# ExternalMotorControllerRev2.net
KiCad netlist of a schematic drawn in EAGLE
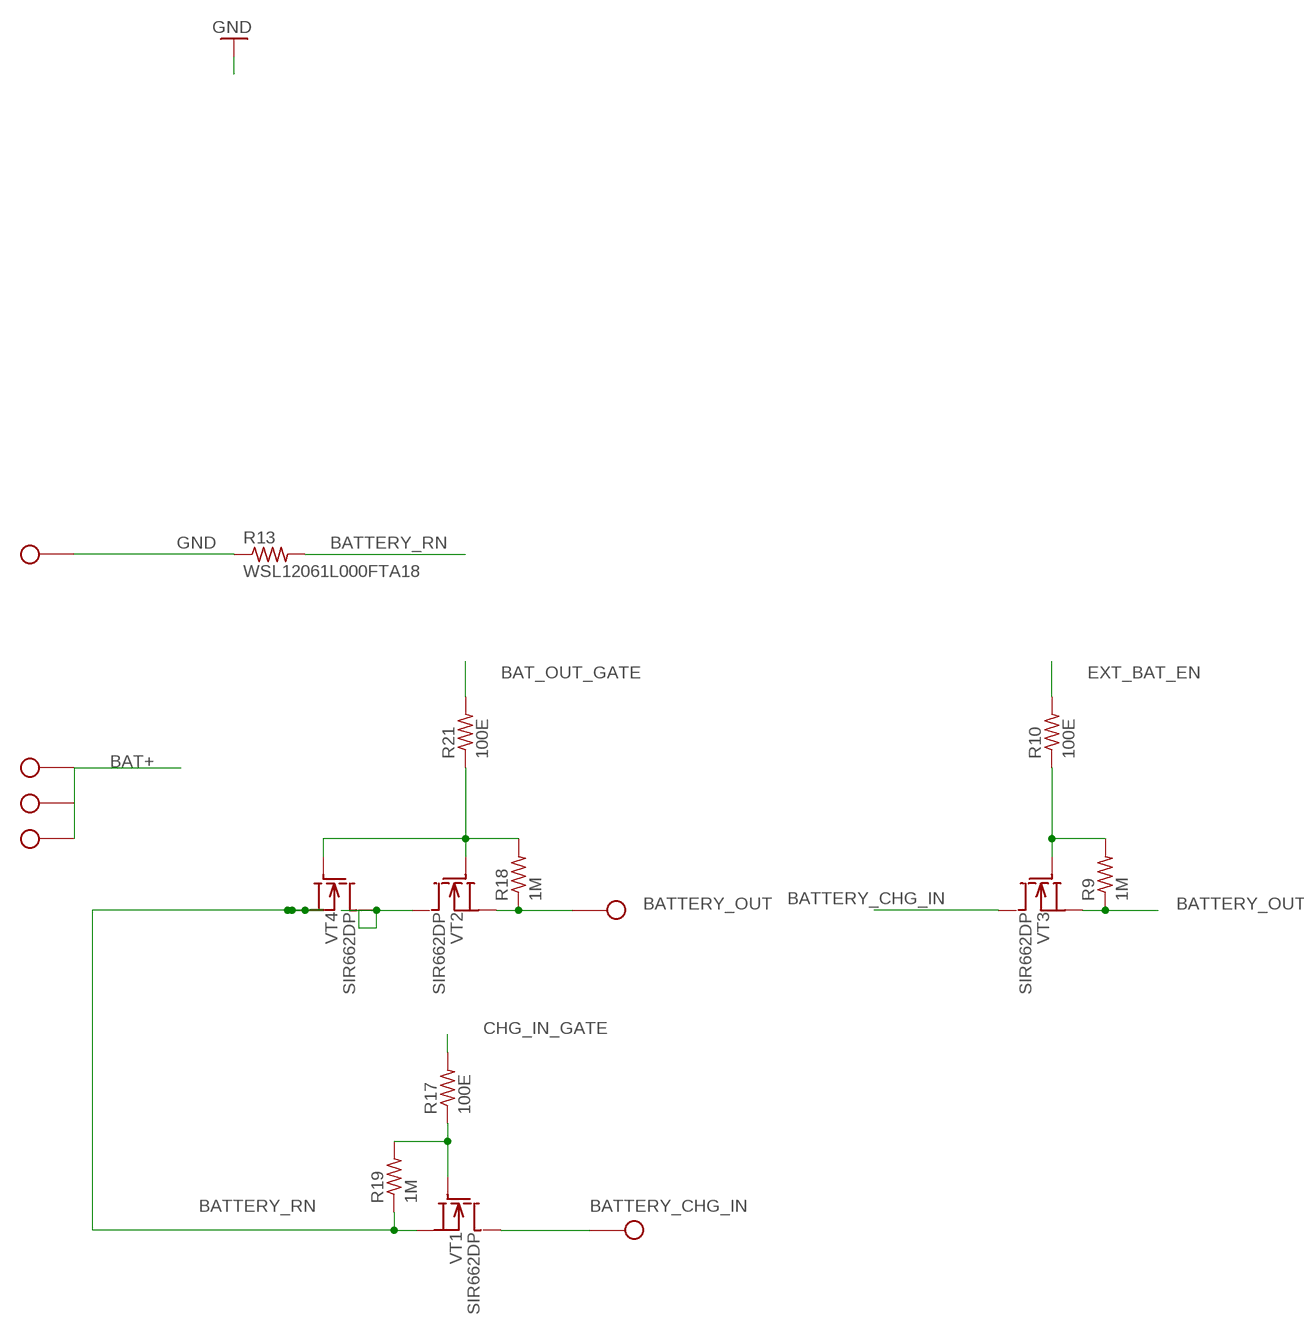
[diagram p0: schematic, sheet 1]
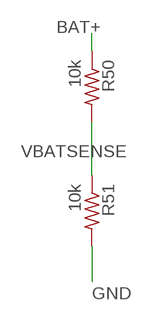
[diagram p1: schematic, sheet 3]
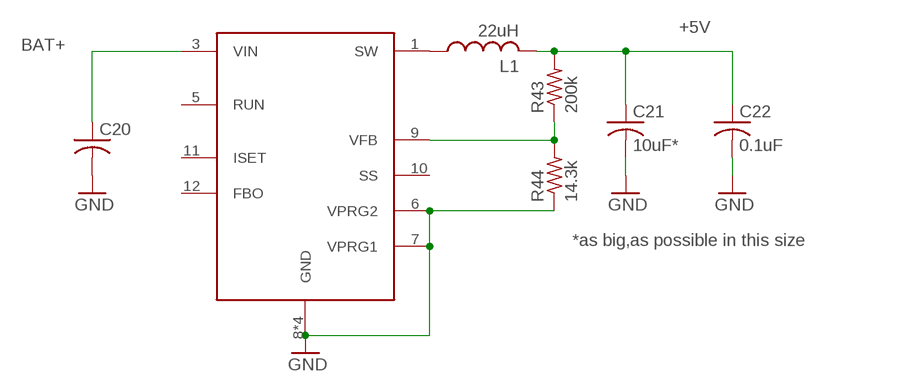
[diagram p2: schematic, sheet 4]
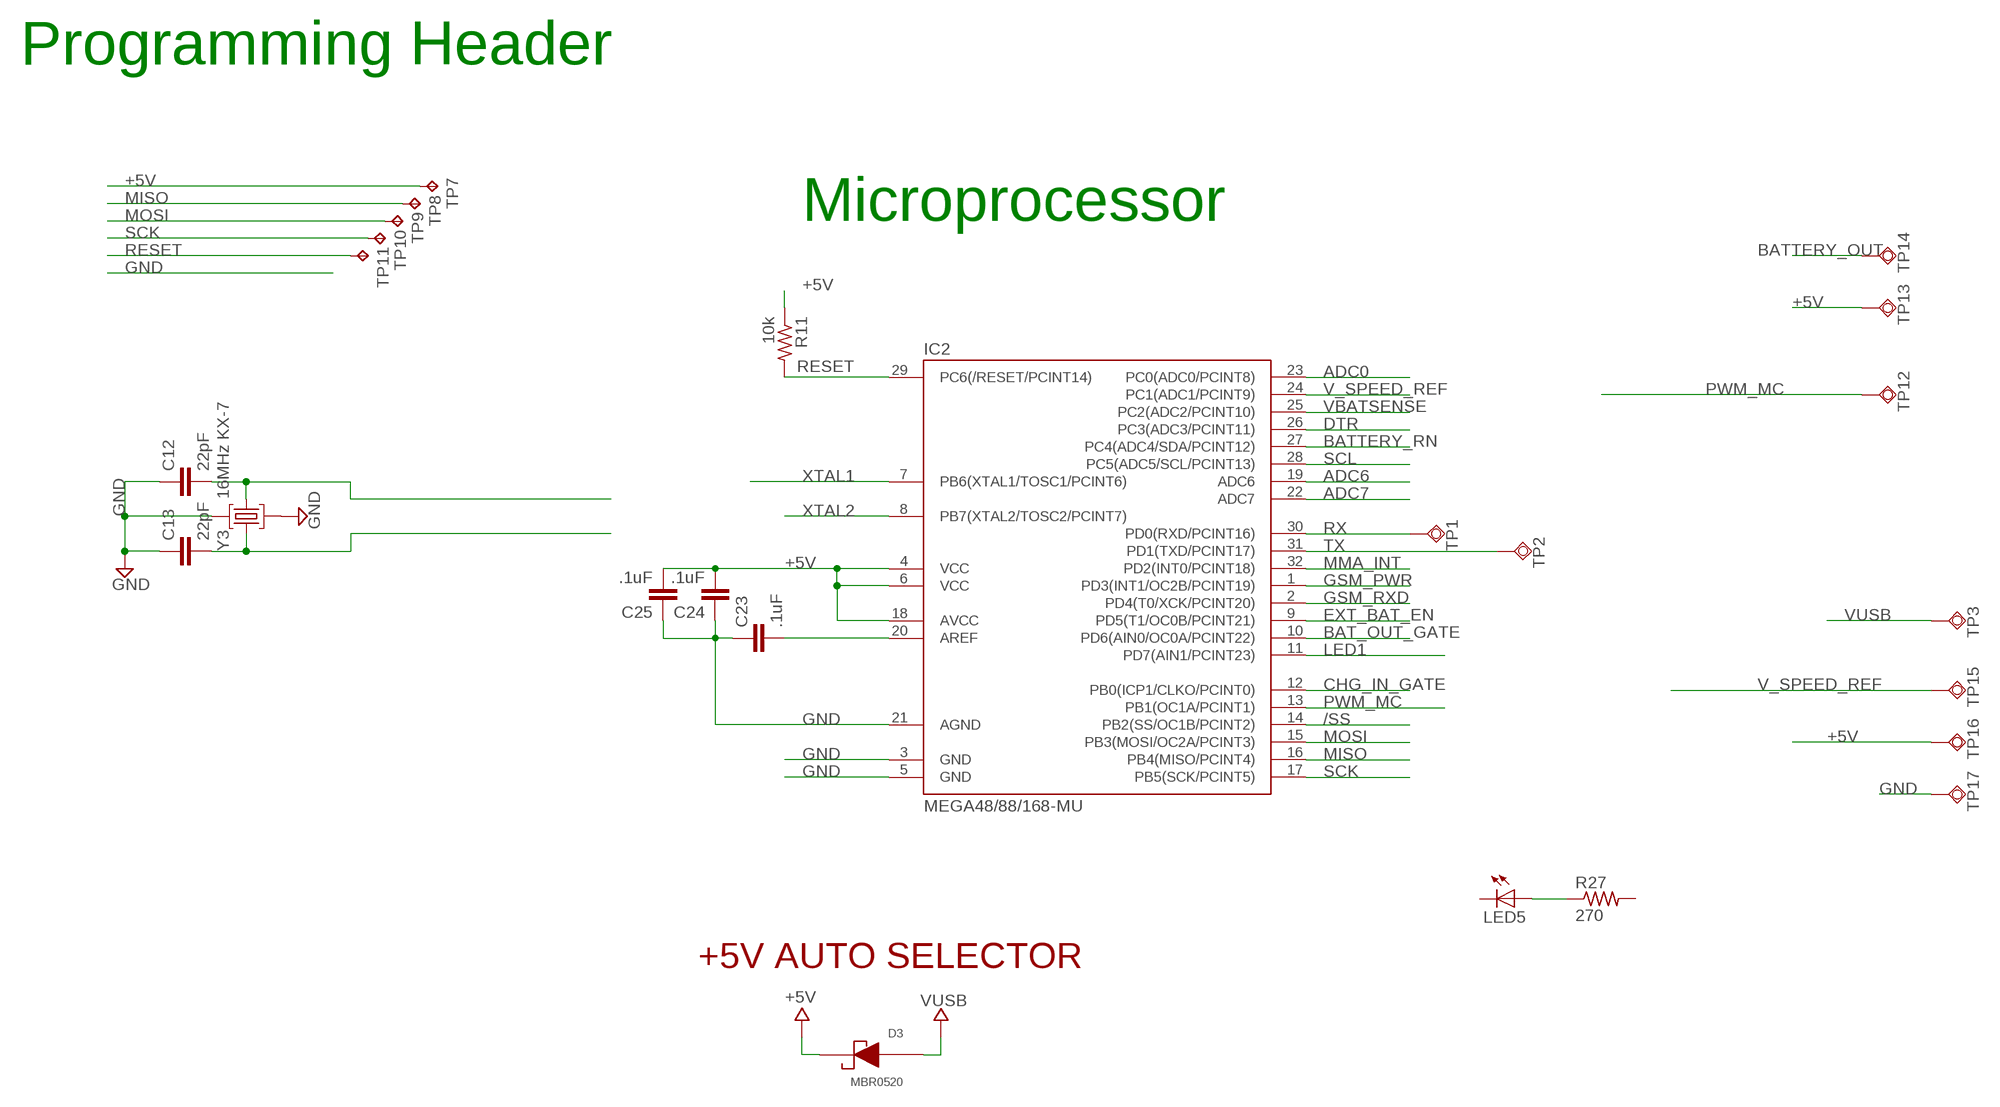
[diagram p3: schematic, sheet 7]

(export (version "E")
  (design (tool "Eeschema 10.0.6"))
  (components
    (comp (ref "R9")
      (value "1M")
      (footprint "eagle-import:R0402")
      (libsource (lib "eagle-import") (part "R-US_R0402"))
    )
    (comp (ref "R10")
      (value "100E")
      (footprint "eagle-import:R0402")
      (libsource (lib "eagle-import") (part "R-US_R0402"))
    )
    (comp (ref "R13")
      (value "WSL12061L000FTA18")
      (footprint "eagle-import:R2512")
      (libsource (lib "eagle-import") (part "R-US_R2512"))
    )
    (comp (ref "R17")
      (value "100E")
      (footprint "eagle-import:R0402")
      (libsource (lib "eagle-import") (part "R-US_R0402"))
    )
    (comp (ref "R18")
      (value "1M")
      (footprint "eagle-import:R0402")
      (libsource (lib "eagle-import") (part "R-US_R0402"))
    )
    (comp (ref "R19")
      (value "1M")
      (footprint "eagle-import:R0402")
      (libsource (lib "eagle-import") (part "R-US_R0402"))
    )
    (comp (ref "R21")
      (value "100E")
      (footprint "eagle-import:R0402")
      (libsource (lib "eagle-import") (part "R-US_R0402"))
    )
    (comp (ref "VT1")
      (value "SIR662DP")
      (footprint "eagle-import:POWERPAK_SO8")
      (libsource (lib "eagle-import") (part "SIR662DP"))
    )
    (comp (ref "VT2")
      (value "SIR662DP")
      (footprint "eagle-import:POWERPAK_SO8")
      (libsource (lib "eagle-import") (part "SIR662DP"))
    )
    (comp (ref "VT3")
      (value "SIR662DP")
      (footprint "eagle-import:POWERPAK_SO8")
      (libsource (lib "eagle-import") (part "SIR662DP"))
    )
    (comp (ref "VT4")
      (value "SIR662DP")
      (footprint "eagle-import:POWERPAK_SO8")
      (libsource (lib "eagle-import") (part "SIR662DP"))
    )
    (comp (ref "X1")
      (value "SOLDER_HOLE18AWG")
      (footprint "eagle-import:SOLDER_HOLE_18")
      (libsource (lib "eagle-import") (part "SOLDER_HOLE18AWG"))
    )
    (comp (ref "X2")
      (value "SOLDER_HOLE18AWG")
      (footprint "eagle-import:SOLDER_HOLE_18")
      (libsource (lib "eagle-import") (part "SOLDER_HOLE18AWG"))
    )
    (comp (ref "X3")
      (value "SOLDER_HOLE18AWG")
      (footprint "eagle-import:SOLDER_HOLE_18")
      (libsource (lib "eagle-import") (part "SOLDER_HOLE18AWG"))
    )
    (comp (ref "X4")
      (value "SOLDER_HOLE18AWG")
      (footprint "eagle-import:SOLDER_HOLE_18")
      (libsource (lib "eagle-import") (part "SOLDER_HOLE18AWG"))
    )
    (comp (ref "X5")
      (value "SOLDER_HOLE18AWG")
      (footprint "eagle-import:SOLDER_HOLE_18")
      (libsource (lib "eagle-import") (part "SOLDER_HOLE18AWG"))
    )
    (comp (ref "X13")
      (value "SOLDER_HOLE18AWG")
      (footprint "eagle-import:SOLDER_HOLE_18")
      (libsource (lib "eagle-import") (part "SOLDER_HOLE18AWG"))
    )
    (comp (ref "R50")
      (value "10k")
      (footprint "eagle-import:R0402")
      (libsource (lib "eagle-import") (part "rcl_R-US_R0402"))
    )
    (comp (ref "R51")
      (value "10k")
      (footprint "eagle-import:R0402")
      (libsource (lib "eagle-import") (part "rcl_R-US_R0402"))
    )
    (comp (ref "C12")
      (value "22pF")
      (footprint "eagle-import:C0402")
      (libsource (lib "eagle-import") (part "C-EUC0402"))
    )
    (comp (ref "C13")
      (value "22pF")
      (footprint "eagle-import:C0402")
      (libsource (lib "eagle-import") (part "C-EUC0402"))
    )
    (comp (ref "C23")
      (value ".1uF")
      (footprint "eagle-import:C0402")
      (libsource (lib "eagle-import") (part "rcl_C-EUC0402"))
    )
    (comp (ref "C24")
      (value ".1uF")
      (footprint "eagle-import:C0402")
      (libsource (lib "eagle-import") (part "rcl_C-EUC0402"))
    )
    (comp (ref "C25")
      (value ".1uF")
      (footprint "eagle-import:C0402")
      (libsource (lib "eagle-import") (part "rcl_C-EUC0402"))
    )
    (comp (ref "D3")
      (value "MBR0520")
      (footprint "eagle-import:SOD-123")
      (libsource (lib "eagle-import") (part "MBR0520"))
    )
    (comp (ref "IC2")
      (value "MEGA48/88/168-MU")
      (footprint "eagle-import:MLF32")
      (libsource (lib "eagle-import") (part "MEGA48/88/168-MU"))
    )
    (comp (ref "LED5")
      (value "LEDCHIP-LED0603")
      (footprint "eagle-import:CHIP-LED0603")
      (libsource (lib "eagle-import") (part "LEDCHIP-LED0603"))
    )
    (comp (ref "R11")
      (value "10k")
      (footprint "eagle-import:R0402")
      (libsource (lib "eagle-import") (part "rcl_R-US_R0402"))
    )
    (comp (ref "R27")
      (value "270")
      (footprint "eagle-import:R0402")
      (libsource (lib "eagle-import") (part "rcl_R-US_R0402"))
    )
    (comp (ref "TP1")
      (value "TPSQTP15R")
      (footprint "eagle-import:TP15R")
      (libsource (lib "eagle-import") (part "TPSQTP15R"))
    )
    (comp (ref "TP2")
      (value "TPSQTP15R")
      (footprint "eagle-import:TP15R")
      (libsource (lib "eagle-import") (part "TPSQTP15R"))
    )
    (comp (ref "TP3")
      (value "TPSQTP15R")
      (footprint "eagle-import:TP15R")
      (libsource (lib "eagle-import") (part "TPSQTP15R"))
    )
    (comp (ref "TP7")
      (value "TPTP08R")
      (footprint "eagle-import:TP08R")
      (libsource (lib "eagle-import") (part "TPTP08R"))
    )
    (comp (ref "TP8")
      (value "TPTP08R")
      (footprint "eagle-import:TP08R")
      (libsource (lib "eagle-import") (part "TPTP08R"))
    )
    (comp (ref "TP9")
      (value "TPTP08R")
      (footprint "eagle-import:TP08R")
      (libsource (lib "eagle-import") (part "TPTP08R"))
    )
    (comp (ref "TP10")
      (value "TPTP08R")
      (footprint "eagle-import:TP08R")
      (libsource (lib "eagle-import") (part "TPTP08R"))
    )
    (comp (ref "TP11")
      (value "TPTP10R")
      (footprint "eagle-import:TP10R")
      (libsource (lib "eagle-import") (part "TPTP10R"))
    )
    (comp (ref "TP12")
      (value "TPSQTP15SQ")
      (footprint "eagle-import:TP15SQ")
      (libsource (lib "eagle-import") (part "TPSQTP15SQ"))
    )
    (comp (ref "TP13")
      (value "TPSQTP15SQ")
      (footprint "eagle-import:TP15SQ")
      (libsource (lib "eagle-import") (part "TPSQTP15SQ"))
    )
    (comp (ref "TP14")
      (value "TPSQTP15SQ")
      (footprint "eagle-import:TP15SQ")
      (libsource (lib "eagle-import") (part "TPSQTP15SQ"))
    )
    (comp (ref "TP15")
      (value "TPSQTP15R")
      (footprint "eagle-import:TP15R")
      (libsource (lib "eagle-import") (part "TPSQTP15R"))
    )
    (comp (ref "TP16")
      (value "TPSQTP15SQ")
      (footprint "eagle-import:TP15SQ")
      (libsource (lib "eagle-import") (part "TPSQTP15SQ"))
    )
    (comp (ref "TP17")
      (value "TPSQTP15SQ")
      (footprint "eagle-import:TP15SQ")
      (libsource (lib "eagle-import") (part "TPSQTP15SQ"))
    )
    (comp (ref "Y3")
      (value "16MHz KX-7")
      (footprint "eagle-import:CRYSTAL-3.2-2.5")
      (libsource (lib "eagle-import") (part "CRYSTAL-3.2-2.5"))
    )
    (comp (ref "C20")
      (value "RCL_C-USC0805")
      (footprint "eagle-import:RCL_C0805$1")
      (libsource (lib "eagle-import") (part "RCL_C-USC0805"))
    )
    (comp (ref "C21")
      (value "10uF*")
      (footprint "eagle-import:RCL_C4532$1")
      (libsource (lib "eagle-import") (part "RCL_C-USC4532"))
    )
    (comp (ref "C22")
      (value "0.1uF")
      (footprint "eagle-import:C0402")
      (libsource (lib "eagle-import") (part "C-USC0402"))
    )
    (comp (ref "DA2")
      (value "LTC3630")
      (footprint "eagle-import:MSE16(12)")
      (libsource (lib "eagle-import") (part "LTC3630"))
    )
    (comp (ref "L1")
      (value "22uH")
      (footprint "eagle-import:M-PAD-2.1_1210")
      (libsource (lib "eagle-import") (part "M-PAD-2.1_L_USD"))
    )
    (comp (ref "R43")
      (value "200k")
      (footprint "eagle-import:RCL_R0402")
      (libsource (lib "eagle-import") (part "RCL_R-US_R0402"))
    )
    (comp (ref "R44")
      (value "14.3k")
      (footprint "eagle-import:RCL_R0402")
      (libsource (lib "eagle-import") (part "RCL_R-US_R0402"))
    )
  )
  (nets
    (net (code "1") (name "+5V") (class "Default")
      (node (ref "C21") (pin "1") (pinfunction "1_1") (pintype "passive"))
      (node (ref "C22") (pin "1") (pinfunction "1_1") (pintype "passive"))
      (node (ref "C24") (pin "2") (pinfunction "2_2") (pintype "passive"))
      (node (ref "C25") (pin "2") (pinfunction "2_2") (pintype "passive"))
      (node (ref "D3") (pin "1") (pinfunction "CA_1") (pintype "passive"))
      (node (ref "IC2") (pin "18") (pinfunction "AVCC_18") (pintype "passive"))
      (node (ref "IC2") (pin "4") (pinfunction "VCC_4") (pintype "power_in"))
      (node (ref "IC2") (pin "6") (pinfunction "VCC_6") (pintype "power_in"))
      (node (ref "L1") (pin "2") (pinfunction "2_2") (pintype "passive"))
      (node (ref "R11") (pin "1") (pinfunction "1_1") (pintype "passive"))
      (node (ref "R43") (pin "2") (pinfunction "2_2") (pintype "passive"))
      (node (ref "TP13") (pin "TP") (pinfunction "TP_TP") (pintype "input"))
      (node (ref "TP16") (pin "TP") (pinfunction "TP_TP") (pintype "input"))
      (node (ref "TP7") (pin "TP") (pinfunction "TP_TP") (pintype "input"))
    )
    (net (code "2") (name "ADC0") (class "Default")
      (node (ref "IC2") (pin "23") (pinfunction "PC0(ADC0/PCINT8)_23") (pintype "bidirectional"))
    )
    (net (code "3") (name "ADC6") (class "Default")
      (node (ref "IC2") (pin "19") (pinfunction "ADC6_19") (pintype "passive"))
    )
    (net (code "4") (name "ADC7") (class "Default")
      (node (ref "IC2") (pin "22") (pinfunction "ADC7_22") (pintype "passive"))
    )
    (net (code "5") (name "BAT+") (class "Default")
      (node (ref "C20") (pin "1") (pinfunction "1_1") (pintype "passive"))
      (node (ref "DA2") (pin "3") (pinfunction "VIN_3") (pintype "power_in"))
      (node (ref "R50") (pin "1") (pinfunction "1_1") (pintype "passive"))
      (node (ref "X1") (pin "1") (pinfunction "P$1_1") (pintype "bidirectional"))
      (node (ref "X4") (pin "1") (pinfunction "P$1_1") (pintype "bidirectional"))
      (node (ref "X5") (pin "1") (pinfunction "P$1_1") (pintype "bidirectional"))
    )
    (net (code "6") (name "BATTERY_CHG_IN") (class "Default")
      (node (ref "VT1") (pin "D") (pinfunction "D_D") (pintype "bidirectional"))
      (node (ref "VT3") (pin "D") (pinfunction "D_D") (pintype "bidirectional"))
      (node (ref "X2") (pin "1") (pinfunction "P$1_1") (pintype "bidirectional"))
    )
    (net (code "7") (name "BATTERY_OUT") (class "Default")
      (node (ref "R18") (pin "1") (pinfunction "1_1") (pintype "passive"))
      (node (ref "R9") (pin "1") (pinfunction "1_1") (pintype "passive"))
      (node (ref "TP14") (pin "TP") (pinfunction "TP_TP") (pintype "input"))
      (node (ref "VT2") (pin "S1") (pinfunction "S_S1") (pintype "bidirectional"))
      (node (ref "VT2") (pin "S2") (pinfunction "S_S2") (pintype "bidirectional"))
      (node (ref "VT2") (pin "S3") (pinfunction "S_S3") (pintype "bidirectional"))
      (node (ref "VT3") (pin "S1") (pinfunction "S_S1") (pintype "bidirectional"))
      (node (ref "VT3") (pin "S2") (pinfunction "S_S2") (pintype "bidirectional"))
      (node (ref "VT3") (pin "S3") (pinfunction "S_S3") (pintype "bidirectional"))
      (node (ref "X3") (pin "1") (pinfunction "P$1_1") (pintype "bidirectional"))
    )
    (net (code "8") (name "BATTERY_RN") (class "Default")
      (node (ref "IC2") (pin "27") (pinfunction "PC4(ADC4/SDA/PCINT12)_27") (pintype "bidirectional"))
      (node (ref "R13") (pin "2") (pinfunction "2_2") (pintype "passive"))
      (node (ref "R19") (pin "1") (pinfunction "1_1") (pintype "passive"))
      (node (ref "VT1") (pin "S1") (pinfunction "S_S1") (pintype "bidirectional"))
      (node (ref "VT1") (pin "S2") (pinfunction "S_S2") (pintype "bidirectional"))
      (node (ref "VT1") (pin "S3") (pinfunction "S_S3") (pintype "bidirectional"))
      (node (ref "VT4") (pin "S1") (pinfunction "S_S1") (pintype "bidirectional"))
      (node (ref "VT4") (pin "S2") (pinfunction "S_S2") (pintype "bidirectional"))
      (node (ref "VT4") (pin "S3") (pinfunction "S_S3") (pintype "bidirectional"))
    )
    (net (code "9") (name "BAT_OUT_GATE") (class "Default")
      (node (ref "IC2") (pin "10") (pinfunction "PD6(AIN0/OC0A/PCINT22)_10") (pintype "bidirectional"))
      (node (ref "R21") (pin "2") (pinfunction "2_2") (pintype "passive"))
    )
    (net (code "10") (name "CHG_IN_GATE") (class "Default")
      (node (ref "IC2") (pin "12") (pinfunction "PB0(ICP1/CLKO/PCINT0)_12") (pintype "bidirectional"))
      (node (ref "R17") (pin "2") (pinfunction "2_2") (pintype "passive"))
    )
    (net (code "11") (name "DTR") (class "Default")
      (node (ref "IC2") (pin "26") (pinfunction "PC3(ADC3/PCINT11)_26") (pintype "bidirectional"))
    )
    (net (code "12") (name "EXT_BAT_EN") (class "Default")
      (node (ref "IC2") (pin "9") (pinfunction "PD5(T1/OC0B/PCINT21)_9") (pintype "bidirectional"))
      (node (ref "R10") (pin "2") (pinfunction "2_2") (pintype "passive"))
    )
    (net (code "13") (name "GND") (class "Default")
      (node (ref "C12") (pin "1") (pinfunction "1_1") (pintype "passive"))
      (node (ref "C13") (pin "1") (pinfunction "1_1") (pintype "passive"))
      (node (ref "C20") (pin "2") (pinfunction "2_2") (pintype "passive"))
      (node (ref "C21") (pin "2") (pinfunction "2_2") (pintype "passive"))
      (node (ref "C22") (pin "2") (pinfunction "2_2") (pintype "passive"))
      (node (ref "C23") (pin "1") (pinfunction "1_1") (pintype "passive"))
      (node (ref "C24") (pin "1") (pinfunction "1_1") (pintype "passive"))
      (node (ref "C25") (pin "1") (pinfunction "1_1") (pintype "passive"))
      (node (ref "DA2") (pin "14") (pinfunction "GND_14") (pintype "bidirectional"))
      (node (ref "DA2") (pin "16") (pinfunction "GND_16") (pintype "bidirectional"))
      (node (ref "DA2") (pin "17") (pinfunction "GND_17") (pintype "bidirectional"))
      (node (ref "DA2") (pin "6") (pinfunction "VPRG2_6") (pintype "input"))
      (node (ref "DA2") (pin "7") (pinfunction "VPRG1_7") (pintype "input"))
      (node (ref "DA2") (pin "8") (pinfunction "GND_8") (pintype "bidirectional"))
      (node (ref "IC2") (pin "21") (pinfunction "AGND_21") (pintype "power_in"))
      (node (ref "IC2") (pin "3") (pinfunction "GND_3") (pintype "power_in"))
      (node (ref "IC2") (pin "5") (pinfunction "GND_5") (pintype "power_in"))
      (node (ref "R13") (pin "1") (pinfunction "1_1") (pintype "passive"))
      (node (ref "R44") (pin "1") (pinfunction "1_1") (pintype "passive"))
      (node (ref "R51") (pin "2") (pinfunction "2_2") (pintype "passive"))
      (node (ref "TP17") (pin "TP") (pinfunction "TP_TP") (pintype "input"))
      (node (ref "X13") (pin "1") (pinfunction "P$1_1") (pintype "bidirectional"))
      (node (ref "Y3") (pin "2") (pinfunction "GND_2") (pintype "passive"))
      (node (ref "Y3") (pin "4") (pinfunction "GND_4") (pintype "passive"))
    )
    (net (code "14") (name "GSM_PWR") (class "Default")
      (node (ref "IC2") (pin "1") (pinfunction "PD3(INT1/OC2B/PCINT19)_1") (pintype "bidirectional"))
    )
    (net (code "15") (name "GSM_RXD") (class "Default")
      (node (ref "IC2") (pin "2") (pinfunction "PD4(T0/XCK/PCINT20)_2") (pintype "bidirectional"))
    )
    (net (code "16") (name "LED1") (class "Default")
      (node (ref "IC2") (pin "11") (pinfunction "PD7(AIN1/PCINT23)_11") (pintype "bidirectional"))
    )
    (net (code "17") (name "MISO") (class "Default")
      (node (ref "IC2") (pin "16") (pinfunction "PB4(MISO/PCINT4)_16") (pintype "bidirectional"))
      (node (ref "TP8") (pin "TP") (pinfunction "TP_TP") (pintype "input"))
    )
    (net (code "18") (name "MMA_INT") (class "Default")
      (node (ref "IC2") (pin "32") (pinfunction "PD2(INT0/PCINT18)_32") (pintype "bidirectional"))
    )
    (net (code "19") (name "MOSI") (class "Default")
      (node (ref "IC2") (pin "15") (pinfunction "PB3(MOSI/OC2A/PCINT3)_15") (pintype "bidirectional"))
      (node (ref "TP9") (pin "TP") (pinfunction "TP_TP") (pintype "input"))
    )
    (net (code "20") (name "Net-(DA2-SW)") (class "Default")
      (node (ref "DA2") (pin "1") (pinfunction "SW_1") (pintype "power_in"))
      (node (ref "L1") (pin "1") (pinfunction "1_1") (pintype "passive"))
    )
    (net (code "21") (name "Net-(DA2-VFB)") (class "Default")
      (node (ref "DA2") (pin "9") (pinfunction "VFB_9") (pintype "input"))
      (node (ref "R43") (pin "1") (pinfunction "1_1") (pintype "passive"))
      (node (ref "R44") (pin "2") (pinfunction "2_2") (pintype "passive"))
    )
    (net (code "22") (name "Net-(IC2-AREF)") (class "Default")
      (node (ref "C23") (pin "2") (pinfunction "2_2") (pintype "passive"))
      (node (ref "IC2") (pin "20") (pinfunction "AREF_20") (pintype "passive"))
    )
    (net (code "23") (name "Net-(LED5-PadA)") (class "Default")
      (node (ref "LED5") (pin "A") (pinfunction "A_A") (pintype "passive"))
      (node (ref "R27") (pin "1") (pinfunction "1_1") (pintype "passive"))
    )
    (net (code "24") (name "Net-(R10-Pad1)") (class "Default")
      (node (ref "R10") (pin "1") (pinfunction "1_1") (pintype "passive"))
      (node (ref "R9") (pin "2") (pinfunction "2_2") (pintype "passive"))
      (node (ref "VT3") (pin "G") (pinfunction "G_G") (pintype "bidirectional"))
    )
    (net (code "25") (name "Net-(R17-Pad1)") (class "Default")
      (node (ref "R17") (pin "1") (pinfunction "1_1") (pintype "passive"))
      (node (ref "R19") (pin "2") (pinfunction "2_2") (pintype "passive"))
      (node (ref "VT1") (pin "G") (pinfunction "G_G") (pintype "bidirectional"))
    )
    (net (code "26") (name "Net-(R18-Pad2)") (class "Default")
      (node (ref "R18") (pin "2") (pinfunction "2_2") (pintype "passive"))
      (node (ref "R21") (pin "1") (pinfunction "1_1") (pintype "passive"))
      (node (ref "VT2") (pin "G") (pinfunction "G_G") (pintype "bidirectional"))
      (node (ref "VT4") (pin "G") (pinfunction "G_G") (pintype "bidirectional"))
    )
    (net (code "27") (name "Net-(VT2-PadD)") (class "Default")
      (node (ref "VT2") (pin "D") (pinfunction "D_D") (pintype "bidirectional"))
      (node (ref "VT4") (pin "D") (pinfunction "D_D") (pintype "bidirectional"))
    )
    (net (code "28") (name "PWM_MC") (class "Default")
      (node (ref "IC2") (pin "13") (pinfunction "PB1(OC1A/PCINT1)_13") (pintype "bidirectional"))
      (node (ref "TP12") (pin "TP") (pinfunction "TP_TP") (pintype "input"))
    )
    (net (code "29") (name "RESET") (class "Default")
      (node (ref "IC2") (pin "29") (pinfunction "PC6(/RESET/PCINT14)_29") (pintype "bidirectional"))
      (node (ref "R11") (pin "2") (pinfunction "2_2") (pintype "passive"))
      (node (ref "TP11") (pin "TP") (pinfunction "TP_TP") (pintype "input"))
    )
    (net (code "30") (name "RX") (class "Default")
      (node (ref "IC2") (pin "30") (pinfunction "PD0(RXD/PCINT16)_30") (pintype "bidirectional"))
      (node (ref "TP1") (pin "TP") (pinfunction "TP_TP") (pintype "input"))
    )
    (net (code "31") (name "SCK") (class "Default")
      (node (ref "IC2") (pin "17") (pinfunction "PB5(SCK/PCINT5)_17") (pintype "bidirectional"))
      (node (ref "TP10") (pin "TP") (pinfunction "TP_TP") (pintype "input"))
    )
    (net (code "32") (name "SCL") (class "Default")
      (node (ref "IC2") (pin "28") (pinfunction "PC5(ADC5/SCL/PCINT13)_28") (pintype "bidirectional"))
    )
    (net (code "33") (name "TX") (class "Default")
      (node (ref "IC2") (pin "31") (pinfunction "PD1(TXD/PCINT17)_31") (pintype "bidirectional"))
      (node (ref "TP2") (pin "TP") (pinfunction "TP_TP") (pintype "input"))
    )
    (net (code "34") (name "VBATSENSE") (class "Default")
      (node (ref "IC2") (pin "25") (pinfunction "PC2(ADC2/PCINT10)_25") (pintype "bidirectional"))
      (node (ref "R50") (pin "2") (pinfunction "2_2") (pintype "passive"))
      (node (ref "R51") (pin "1") (pinfunction "1_1") (pintype "passive"))
    )
    (net (code "35") (name "VUSB") (class "Default")
      (node (ref "D3") (pin "2") (pinfunction "AN_2") (pintype "passive"))
      (node (ref "TP3") (pin "TP") (pinfunction "TP_TP") (pintype "input"))
    )
    (net (code "36") (name "V_SPEED_REF") (class "Default")
      (node (ref "IC2") (pin "24") (pinfunction "PC1(ADC1/PCINT9)_24") (pintype "bidirectional"))
      (node (ref "TP15") (pin "TP") (pinfunction "TP_TP") (pintype "input"))
    )
    (net (code "37") (name "XTAL1") (class "Default")
      (node (ref "C13") (pin "2") (pinfunction "2_2") (pintype "passive"))
      (node (ref "IC2") (pin "7") (pinfunction "PB6(XTAL1/TOSC1/PCINT6)_7") (pintype "bidirectional"))
      (node (ref "Y3") (pin "3") (pinfunction "C2_3") (pintype "passive"))
    )
    (net (code "38") (name "XTAL2") (class "Default")
      (node (ref "C12") (pin "2") (pinfunction "2_2") (pintype "passive"))
      (node (ref "IC2") (pin "8") (pinfunction "PB7(XTAL2/TOSC2/PCINT7)_8") (pintype "bidirectional"))
      (node (ref "Y3") (pin "1") (pinfunction "C1_1") (pintype "passive"))
    )
    (net (code "39") (name "unconnected-(DA2-FBO-Pad12)") (class "Default")
      (node (ref "DA2") (pin "12") (pinfunction "FBO_12") (pintype "input"))
    )
    (net (code "40") (name "unconnected-(DA2-ISET-Pad11)") (class "Default")
      (node (ref "DA2") (pin "11") (pinfunction "ISET_11") (pintype "input"))
    )
    (net (code "41") (name "unconnected-(DA2-RUN-Pad5)") (class "Default")
      (node (ref "DA2") (pin "5") (pinfunction "RUN_5") (pintype "input"))
    )
    (net (code "42") (name "unconnected-(DA2-SS-Pad10)") (class "Default")
      (node (ref "DA2") (pin "10") (pinfunction "SS_10") (pintype "input"))
    )
    (net (code "43") (name "unconnected-(LED5-PadC)") (class "Default")
      (node (ref "LED5") (pin "C") (pinfunction "C_C") (pintype "passive"))
    )
    (net (code "44") (name "unconnected-(R27-Pad2)") (class "Default")
      (node (ref "R27") (pin "2") (pinfunction "2_2") (pintype "passive"))
    )
    (net (code "45") (name "{slash}SS") (class "Default")
      (node (ref "IC2") (pin "14") (pinfunction "PB2(SS/OC1B/PCINT2)_14") (pintype "bidirectional"))
    )
  )
)
